# R602H.net
KiCad netlist of a schematic drawn in EAGLE
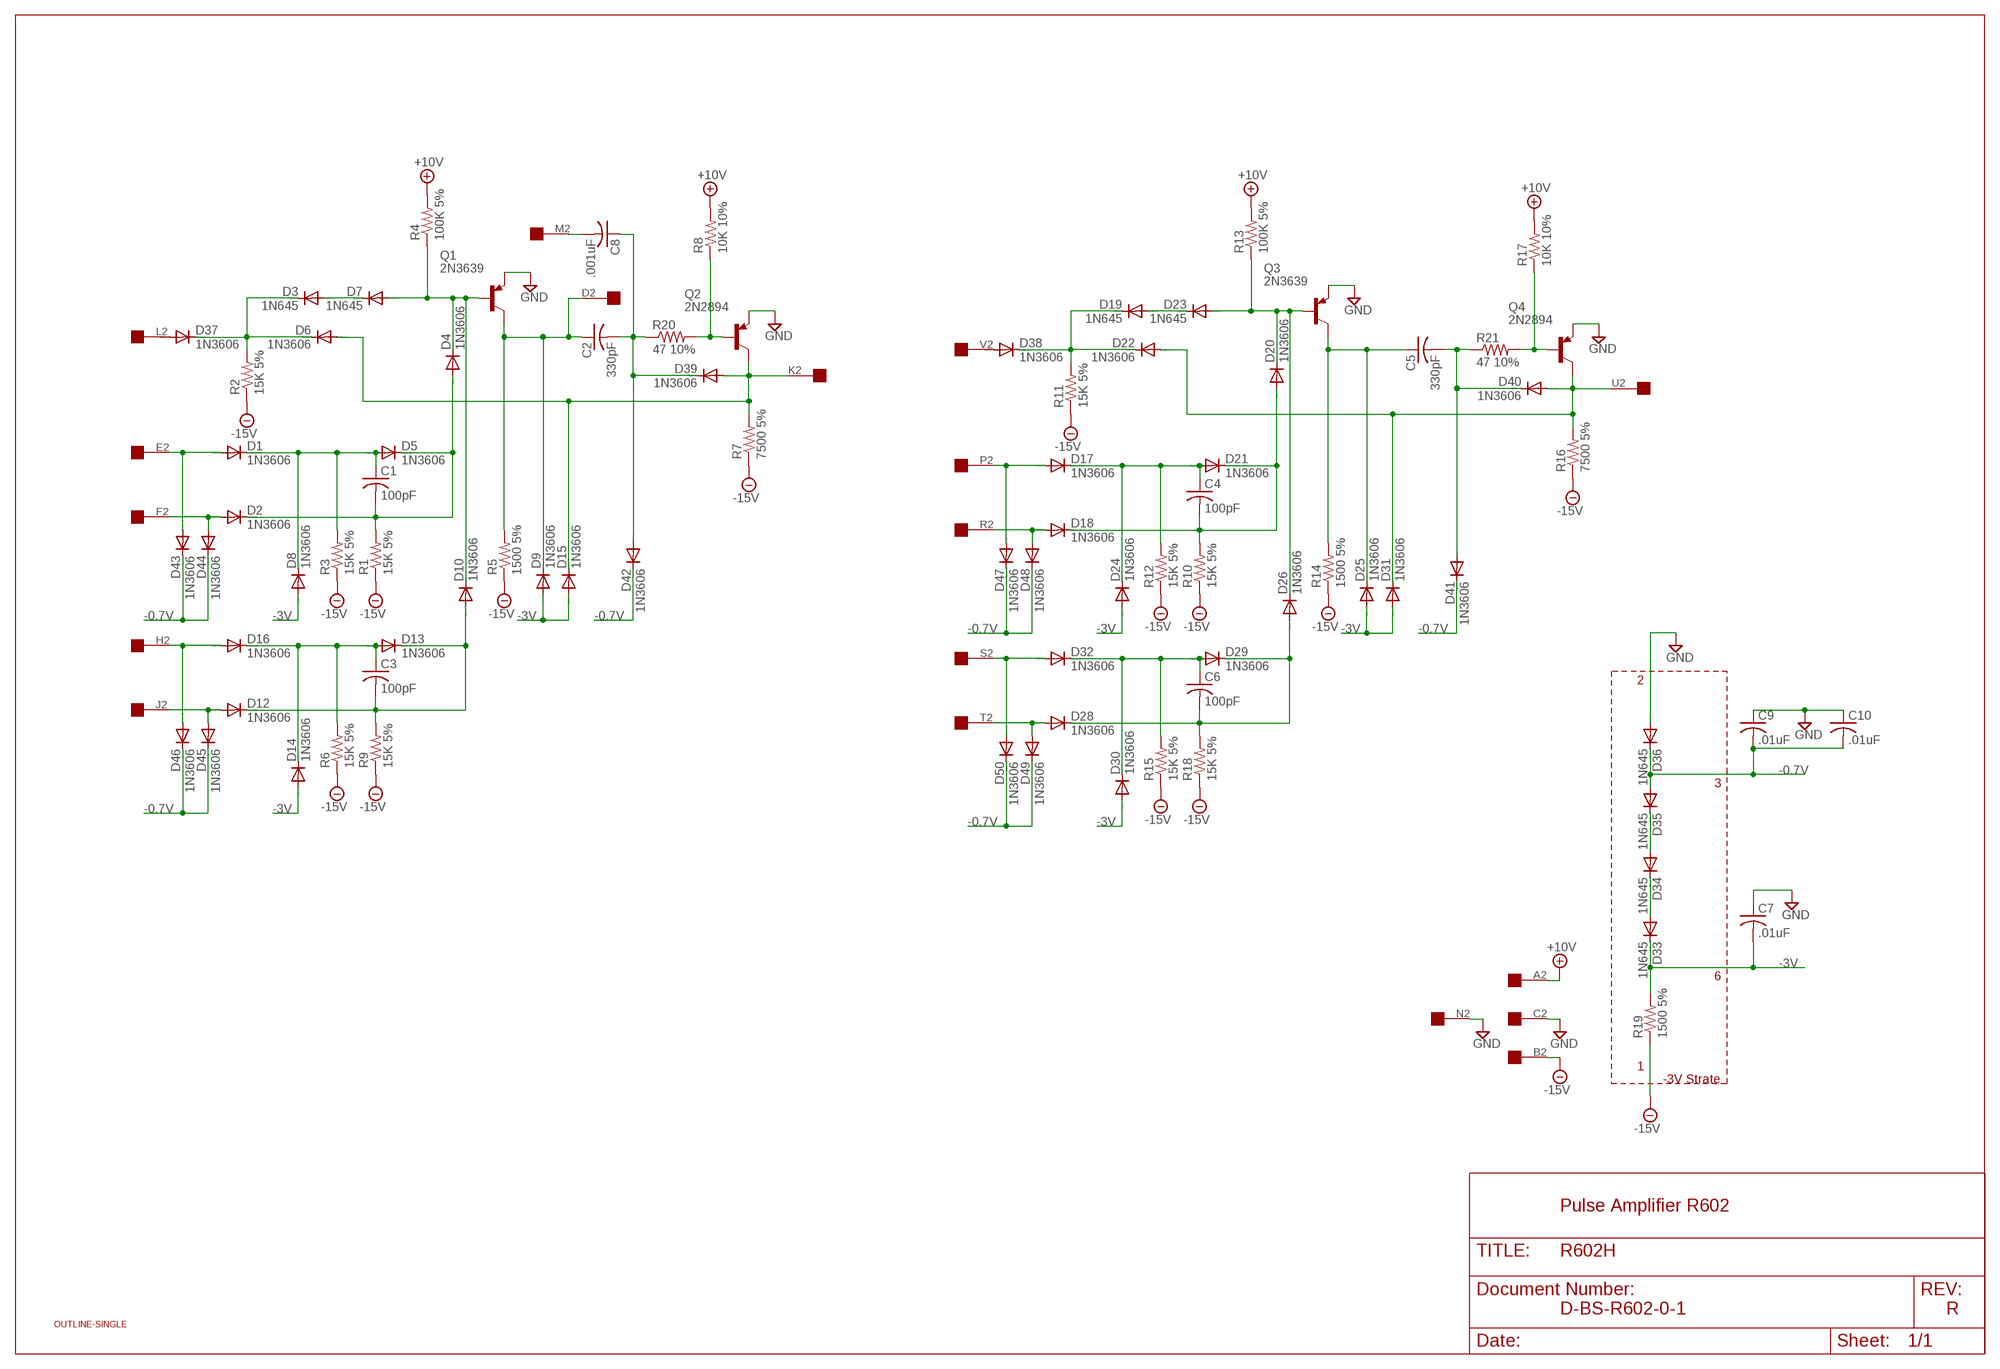
[diagram p0: schematic, sheet 1]

(export (version "E")
  (design (tool "Eeschema 10.0.6"))
  (components
    (comp (ref "C1")
      (value "100pF")
      (footprint "eagle-import:C050-025X075")
      (libsource (lib "eagle-import") (part "C-US050-025X075"))
    )
    (comp (ref "C2")
      (value "330pF")
      (footprint "eagle-import:C050-025X075")
      (libsource (lib "eagle-import") (part "C-US050-025X075"))
    )
    (comp (ref "C3")
      (value "100pF")
      (footprint "eagle-import:C050-025X075")
      (libsource (lib "eagle-import") (part "C-US050-025X075"))
    )
    (comp (ref "C4")
      (value "100pF")
      (footprint "eagle-import:C050-025X075")
      (libsource (lib "eagle-import") (part "C-US050-025X075"))
    )
    (comp (ref "C5")
      (value "330pF")
      (footprint "eagle-import:C050-025X075")
      (libsource (lib "eagle-import") (part "C-US050-025X075"))
    )
    (comp (ref "C6")
      (value "100pF")
      (footprint "eagle-import:C050-025X075")
      (libsource (lib "eagle-import") (part "C-US050-025X075"))
    )
    (comp (ref "C7")
      (value ".01uF")
      (footprint "eagle-import:C075-032X103")
      (libsource (lib "eagle-import") (part "C-US075-032X103"))
    )
    (comp (ref "C8")
      (value ".001uF")
      (footprint "eagle-import:C050-025X075")
      (libsource (lib "eagle-import") (part "C-US050-025X075"))
    )
    (comp (ref "C9")
      (value ".01uF")
      (footprint "eagle-import:C050-025X075")
      (libsource (lib "eagle-import") (part "C-US050-025X075"))
    )
    (comp (ref "C10")
      (value ".01uF")
      (footprint "eagle-import:C050-025X075")
      (libsource (lib "eagle-import") (part "C-US050-025X075"))
    )
    (comp (ref "D1")
      (value "1N3606")
      (footprint "eagle-import:DO35-10")
      (libsource (lib "eagle-import") (part "1N4148DO35-10"))
    )
    (comp (ref "D2")
      (value "1N3606")
      (footprint "eagle-import:DO35-10")
      (libsource (lib "eagle-import") (part "1N4148DO35-10"))
    )
    (comp (ref "D3")
      (value "1N645")
      (footprint "eagle-import:DO35-10")
      (libsource (lib "eagle-import") (part "1N4148DO35-10"))
    )
    (comp (ref "D4")
      (value "1N3606")
      (footprint "eagle-import:DO35-10")
      (libsource (lib "eagle-import") (part "1N4148DO35-10"))
    )
    (comp (ref "D5")
      (value "1N3606")
      (footprint "eagle-import:DO35-10")
      (libsource (lib "eagle-import") (part "1N4148DO35-10"))
    )
    (comp (ref "D6")
      (value "1N3606")
      (footprint "eagle-import:DO35-10")
      (libsource (lib "eagle-import") (part "1N4148DO35-10"))
    )
    (comp (ref "D7")
      (value "1N645")
      (footprint "eagle-import:DO35-10")
      (libsource (lib "eagle-import") (part "1N4148DO35-10"))
    )
    (comp (ref "D8")
      (value "1N3606")
      (footprint "eagle-import:DO35-10")
      (libsource (lib "eagle-import") (part "1N4148DO35-10"))
    )
    (comp (ref "D9")
      (value "1N3606")
      (footprint "eagle-import:DO35-10")
      (libsource (lib "eagle-import") (part "1N4148DO35-10"))
    )
    (comp (ref "D10")
      (value "1N3606")
      (footprint "eagle-import:DO35-10")
      (libsource (lib "eagle-import") (part "1N4148DO35-10"))
    )
    (comp (ref "D12")
      (value "1N3606")
      (footprint "eagle-import:DO35-10")
      (libsource (lib "eagle-import") (part "1N4148DO35-10"))
    )
    (comp (ref "D13")
      (value "1N3606")
      (footprint "eagle-import:DO35-10")
      (libsource (lib "eagle-import") (part "1N4148DO35-10"))
    )
    (comp (ref "D14")
      (value "1N3606")
      (footprint "eagle-import:DO35-10")
      (libsource (lib "eagle-import") (part "1N4148DO35-10"))
    )
    (comp (ref "D15")
      (value "1N3606")
      (footprint "eagle-import:DO35-10")
      (libsource (lib "eagle-import") (part "1N4148DO35-10"))
    )
    (comp (ref "D16")
      (value "1N3606")
      (footprint "eagle-import:DO35-10")
      (libsource (lib "eagle-import") (part "1N4148DO35-10"))
    )
    (comp (ref "D17")
      (value "1N3606")
      (footprint "eagle-import:DO35-10")
      (libsource (lib "eagle-import") (part "1N4148DO35-10"))
    )
    (comp (ref "D18")
      (value "1N3606")
      (footprint "eagle-import:DO35-10")
      (libsource (lib "eagle-import") (part "1N4148DO35-10"))
    )
    (comp (ref "D19")
      (value "1N645")
      (footprint "eagle-import:DO35-10")
      (libsource (lib "eagle-import") (part "1N4148DO35-10"))
    )
    (comp (ref "D20")
      (value "1N3606")
      (footprint "eagle-import:DO35-10")
      (libsource (lib "eagle-import") (part "1N4148DO35-10"))
    )
    (comp (ref "D21")
      (value "1N3606")
      (footprint "eagle-import:DO35-10")
      (libsource (lib "eagle-import") (part "1N4148DO35-10"))
    )
    (comp (ref "D22")
      (value "1N3606")
      (footprint "eagle-import:DO35-10")
      (libsource (lib "eagle-import") (part "1N4148DO35-10"))
    )
    (comp (ref "D23")
      (value "1N645")
      (footprint "eagle-import:DO35-10")
      (libsource (lib "eagle-import") (part "1N4148DO35-10"))
    )
    (comp (ref "D24")
      (value "1N3606")
      (footprint "eagle-import:DO35-10")
      (libsource (lib "eagle-import") (part "1N4148DO35-10"))
    )
    (comp (ref "D25")
      (value "1N3606")
      (footprint "eagle-import:DO35-10")
      (libsource (lib "eagle-import") (part "1N4148DO35-10"))
    )
    (comp (ref "D26")
      (value "1N3606")
      (footprint "eagle-import:DO35-10")
      (libsource (lib "eagle-import") (part "1N4148DO35-10"))
    )
    (comp (ref "D28")
      (value "1N3606")
      (footprint "eagle-import:DO35-10")
      (libsource (lib "eagle-import") (part "1N4148DO35-10"))
    )
    (comp (ref "D29")
      (value "1N3606")
      (footprint "eagle-import:DO35-10")
      (libsource (lib "eagle-import") (part "1N4148DO35-10"))
    )
    (comp (ref "D30")
      (value "1N3606")
      (footprint "eagle-import:DO35-10")
      (libsource (lib "eagle-import") (part "1N4148DO35-10"))
    )
    (comp (ref "D31")
      (value "1N3606")
      (footprint "eagle-import:DO35-10")
      (libsource (lib "eagle-import") (part "1N4148DO35-10"))
    )
    (comp (ref "D32")
      (value "1N3606")
      (footprint "eagle-import:DO35-10")
      (libsource (lib "eagle-import") (part "1N4148DO35-10"))
    )
    (comp (ref "D33")
      (value "1N645")
      (footprint "eagle-import:DO35-10")
      (libsource (lib "eagle-import") (part "1N4148DO35-10"))
    )
    (comp (ref "D34")
      (value "1N645")
      (footprint "eagle-import:DO35-10")
      (libsource (lib "eagle-import") (part "1N4148DO35-10"))
    )
    (comp (ref "D35")
      (value "1N645")
      (footprint "eagle-import:DO35-10")
      (libsource (lib "eagle-import") (part "1N4148DO35-10"))
    )
    (comp (ref "D36")
      (value "1N645")
      (footprint "eagle-import:DO35-10")
      (libsource (lib "eagle-import") (part "1N4148DO35-10"))
    )
    (comp (ref "D37")
      (value "1N3606")
      (footprint "eagle-import:DO35-10")
      (libsource (lib "eagle-import") (part "1N4148DO35-10"))
    )
    (comp (ref "D38")
      (value "1N3606")
      (footprint "eagle-import:DO35-10")
      (libsource (lib "eagle-import") (part "1N4148DO35-10"))
    )
    (comp (ref "D39")
      (value "1N3606")
      (footprint "eagle-import:DO35-10")
      (libsource (lib "eagle-import") (part "1N4148DO35-10"))
    )
    (comp (ref "D40")
      (value "1N3606")
      (footprint "eagle-import:DO35-10")
      (libsource (lib "eagle-import") (part "1N4148DO35-10"))
    )
    (comp (ref "D41")
      (value "1N3606")
      (footprint "eagle-import:DO35-10")
      (libsource (lib "eagle-import") (part "1N4148DO35-10"))
    )
    (comp (ref "D42")
      (value "1N3606")
      (footprint "eagle-import:DO35-10")
      (libsource (lib "eagle-import") (part "1N4148DO35-10"))
    )
    (comp (ref "D43")
      (value "1N3606")
      (footprint "eagle-import:DO35-10")
      (libsource (lib "eagle-import") (part "1N4148DO35-10"))
    )
    (comp (ref "D44")
      (value "1N3606")
      (footprint "eagle-import:DO35-10")
      (libsource (lib "eagle-import") (part "1N4148DO35-10"))
    )
    (comp (ref "D45")
      (value "1N3606")
      (footprint "eagle-import:DO35-10")
      (libsource (lib "eagle-import") (part "1N4148DO35-10"))
    )
    (comp (ref "D46")
      (value "1N3606")
      (footprint "eagle-import:DO35-10")
      (libsource (lib "eagle-import") (part "1N4148DO35-10"))
    )
    (comp (ref "D47")
      (value "1N3606")
      (footprint "eagle-import:DO35-10")
      (libsource (lib "eagle-import") (part "1N4148DO35-10"))
    )
    (comp (ref "D48")
      (value "1N3606")
      (footprint "eagle-import:DO35-10")
      (libsource (lib "eagle-import") (part "1N4148DO35-10"))
    )
    (comp (ref "D49")
      (value "1N3606")
      (footprint "eagle-import:DO35-10")
      (libsource (lib "eagle-import") (part "1N4148DO35-10"))
    )
    (comp (ref "D50")
      (value "1N3606")
      (footprint "eagle-import:DO35-10")
      (libsource (lib "eagle-import") (part "1N4148DO35-10"))
    )
    (comp (ref "Q1")
      (value "2N3639")
      (footprint "eagle-import:TO39")
      (libsource (lib "eagle-import") (part "2N2904"))
    )
    (comp (ref "Q2")
      (value "2N2894")
      (footprint "eagle-import:TO39")
      (libsource (lib "eagle-import") (part "2N2904"))
    )
    (comp (ref "Q3")
      (value "2N3639")
      (footprint "eagle-import:TO39")
      (libsource (lib "eagle-import") (part "2N2904"))
    )
    (comp (ref "Q4")
      (value "2N2894")
      (footprint "eagle-import:TO39")
      (libsource (lib "eagle-import") (part "2N2904"))
    )
    (comp (ref "R1")
      (value "15K 5%")
      (footprint "eagle-import:0207_10")
      (libsource (lib "eagle-import") (part "R-US_0207/10"))
    )
    (comp (ref "R2")
      (value "15K 5%")
      (footprint "eagle-import:0207_10")
      (libsource (lib "eagle-import") (part "R-US_0207/10"))
    )
    (comp (ref "R3")
      (value "15K 5%")
      (footprint "eagle-import:0207_10")
      (libsource (lib "eagle-import") (part "R-US_0207/10"))
    )
    (comp (ref "R4")
      (value "100K 5%")
      (footprint "eagle-import:0207_10")
      (libsource (lib "eagle-import") (part "R-US_0207/10"))
    )
    (comp (ref "R5")
      (value "1500 5%")
      (footprint "eagle-import:0207_10")
      (libsource (lib "eagle-import") (part "R-US_0207/10"))
    )
    (comp (ref "R6")
      (value "15K 5%")
      (footprint "eagle-import:0207_10")
      (libsource (lib "eagle-import") (part "R-US_0207/10"))
    )
    (comp (ref "R7")
      (value "7500 5%")
      (footprint "eagle-import:0207_10")
      (libsource (lib "eagle-import") (part "R-US_0207/10"))
    )
    (comp (ref "R8")
      (value "10K 10%")
      (footprint "eagle-import:0207_10")
      (libsource (lib "eagle-import") (part "R-US_0207/10"))
    )
    (comp (ref "R9")
      (value "15K 5%")
      (footprint "eagle-import:0207_10")
      (libsource (lib "eagle-import") (part "R-US_0207/10"))
    )
    (comp (ref "R10")
      (value "15K 5%")
      (footprint "eagle-import:0207_10")
      (libsource (lib "eagle-import") (part "R-US_0207/10"))
    )
    (comp (ref "R11")
      (value "15K 5%")
      (footprint "eagle-import:0207_10")
      (libsource (lib "eagle-import") (part "R-US_0207/10"))
    )
    (comp (ref "R12")
      (value "15K 5%")
      (footprint "eagle-import:0207_10")
      (libsource (lib "eagle-import") (part "R-US_0207/10"))
    )
    (comp (ref "R13")
      (value "100K 5%")
      (footprint "eagle-import:0207_10")
      (libsource (lib "eagle-import") (part "R-US_0207/10"))
    )
    (comp (ref "R14")
      (value "1500 5%")
      (footprint "eagle-import:0207_10")
      (libsource (lib "eagle-import") (part "R-US_0207/10"))
    )
    (comp (ref "R15")
      (value "15K 5%")
      (footprint "eagle-import:0207_10")
      (libsource (lib "eagle-import") (part "R-US_0207/10"))
    )
    (comp (ref "R16")
      (value "7500 5%")
      (footprint "eagle-import:0207_10")
      (libsource (lib "eagle-import") (part "R-US_0207/10"))
    )
    (comp (ref "R17")
      (value "10K 10%")
      (footprint "eagle-import:0207_10")
      (libsource (lib "eagle-import") (part "R-US_0207/10"))
    )
    (comp (ref "R18")
      (value "15K 5%")
      (footprint "eagle-import:0207_10")
      (libsource (lib "eagle-import") (part "R-US_0207/10"))
    )
    (comp (ref "R19")
      (value "1500 5%")
      (footprint "eagle-import:0207_10")
      (libsource (lib "eagle-import") (part "R-US_0207/10"))
    )
    (comp (ref "R20")
      (value "47 10%")
      (footprint "eagle-import:0207_10")
      (libsource (lib "eagle-import") (part "R-US_0207/10"))
    )
    (comp (ref "R21")
      (value "47 10%")
      (footprint "eagle-import:0207_10")
      (libsource (lib "eagle-import") (part "R-US_0207/10"))
    )
    (comp (ref "U$1")
      (value "OUTLINE-SINGLE")
      (footprint "eagle-import:SINGLE")
      (libsource (lib "eagle-import") (part "OUTLINE-SINGLE"))
    )
    (comp (ref "U$2")
      (value "EDGE-1")
      (footprint "eagle-import:EDGE-CON1")
      (libsource (lib "eagle-import") (part "EDGE-1"))
    )
  )
  (nets
    (net (code "1") (name "+10V") (class "Default")
      (node (ref "R13") (pin "2") (pinfunction "2_2") (pintype "passive"))
      (node (ref "R17") (pin "2") (pinfunction "2_2") (pintype "passive"))
      (node (ref "R4") (pin "2") (pinfunction "2_2") (pintype "passive"))
      (node (ref "R8") (pin "2") (pinfunction "2_2") (pintype "passive"))
      (node (ref "U$2") (pin "A2") (pinfunction "1_A2") (pintype "bidirectional"))
    )
    (net (code "2") (name "-15V") (class "Default")
      (node (ref "R1") (pin "1") (pinfunction "1_1") (pintype "passive"))
      (node (ref "R10") (pin "1") (pinfunction "1_1") (pintype "passive"))
      (node (ref "R11") (pin "1") (pinfunction "1_1") (pintype "passive"))
      (node (ref "R12") (pin "1") (pinfunction "1_1") (pintype "passive"))
      (node (ref "R14") (pin "1") (pinfunction "1_1") (pintype "passive"))
      (node (ref "R15") (pin "1") (pinfunction "1_1") (pintype "passive"))
      (node (ref "R16") (pin "1") (pinfunction "1_1") (pintype "passive"))
      (node (ref "R18") (pin "1") (pinfunction "1_1") (pintype "passive"))
      (node (ref "R19") (pin "1") (pinfunction "1_1") (pintype "passive"))
      (node (ref "R2") (pin "1") (pinfunction "1_1") (pintype "passive"))
      (node (ref "R3") (pin "1") (pinfunction "1_1") (pintype "passive"))
      (node (ref "R5") (pin "1") (pinfunction "1_1") (pintype "passive"))
      (node (ref "R6") (pin "1") (pinfunction "1_1") (pintype "passive"))
      (node (ref "R7") (pin "1") (pinfunction "1_1") (pintype "passive"))
      (node (ref "R9") (pin "1") (pinfunction "1_1") (pintype "passive"))
      (node (ref "U$2") (pin "B2") (pinfunction "1_B2") (pintype "bidirectional"))
    )
    (net (code "3") (name "/-0.7V") (class "Default")
      (node (ref "C10") (pin "2") (pinfunction "2_2") (pintype "passive"))
      (node (ref "C9") (pin "2") (pinfunction "2_2") (pintype "passive"))
      (node (ref "D35") (pin "A") (pinfunction "A_A") (pintype "passive"))
      (node (ref "D36") (pin "C") (pinfunction "C_C") (pintype "passive"))
      (node (ref "D41") (pin "C") (pinfunction "C_C") (pintype "passive"))
      (node (ref "D42") (pin "C") (pinfunction "C_C") (pintype "passive"))
      (node (ref "D43") (pin "C") (pinfunction "C_C") (pintype "passive"))
      (node (ref "D44") (pin "C") (pinfunction "C_C") (pintype "passive"))
      (node (ref "D45") (pin "C") (pinfunction "C_C") (pintype "passive"))
      (node (ref "D46") (pin "C") (pinfunction "C_C") (pintype "passive"))
      (node (ref "D47") (pin "C") (pinfunction "C_C") (pintype "passive"))
      (node (ref "D48") (pin "C") (pinfunction "C_C") (pintype "passive"))
      (node (ref "D49") (pin "C") (pinfunction "C_C") (pintype "passive"))
      (node (ref "D50") (pin "C") (pinfunction "C_C") (pintype "passive"))
    )
    (net (code "4") (name "/-3V") (class "Default")
      (node (ref "C7") (pin "2") (pinfunction "2_2") (pintype "passive"))
      (node (ref "D14") (pin "A") (pinfunction "A_A") (pintype "passive"))
      (node (ref "D15") (pin "A") (pinfunction "A_A") (pintype "passive"))
      (node (ref "D24") (pin "A") (pinfunction "A_A") (pintype "passive"))
      (node (ref "D25") (pin "A") (pinfunction "A_A") (pintype "passive"))
      (node (ref "D30") (pin "A") (pinfunction "A_A") (pintype "passive"))
      (node (ref "D31") (pin "A") (pinfunction "A_A") (pintype "passive"))
      (node (ref "D33") (pin "C") (pinfunction "C_C") (pintype "passive"))
      (node (ref "D8") (pin "A") (pinfunction "A_A") (pintype "passive"))
      (node (ref "D9") (pin "A") (pinfunction "A_A") (pintype "passive"))
      (node (ref "R19") (pin "2") (pinfunction "2_2") (pintype "passive"))
    )
    (net (code "5") (name "GND") (class "Default")
      (node (ref "C10") (pin "1") (pinfunction "1_1") (pintype "passive"))
      (node (ref "C7") (pin "1") (pinfunction "1_1") (pintype "passive"))
      (node (ref "C9") (pin "1") (pinfunction "1_1") (pintype "passive"))
      (node (ref "D36") (pin "A") (pinfunction "A_A") (pintype "passive"))
      (node (ref "Q1") (pin "1") (pinfunction "E_1") (pintype "passive"))
      (node (ref "Q2") (pin "1") (pinfunction "E_1") (pintype "passive"))
      (node (ref "Q3") (pin "1") (pinfunction "E_1") (pintype "passive"))
      (node (ref "Q4") (pin "1") (pinfunction "E_1") (pintype "passive"))
      (node (ref "U$2") (pin "C2") (pinfunction "1_C2") (pintype "bidirectional"))
      (node (ref "U$2") (pin "N2") (pinfunction "1_N2") (pintype "bidirectional"))
    )
    (net (code "6") (name "Net-(C1-Pad1)") (class "Default")
      (node (ref "C1") (pin "1") (pinfunction "1_1") (pintype "passive"))
      (node (ref "D1") (pin "C") (pinfunction "C_C") (pintype "passive"))
      (node (ref "D5") (pin "A") (pinfunction "A_A") (pintype "passive"))
      (node (ref "D8") (pin "C") (pinfunction "C_C") (pintype "passive"))
      (node (ref "R3") (pin "2") (pinfunction "2_2") (pintype "passive"))
    )
    (net (code "7") (name "Net-(C1-Pad2)") (class "Default")
      (node (ref "C1") (pin "2") (pinfunction "2_2") (pintype "passive"))
      (node (ref "D2") (pin "C") (pinfunction "C_C") (pintype "passive"))
      (node (ref "D4") (pin "A") (pinfunction "A_A") (pintype "passive"))
      (node (ref "D5") (pin "C") (pinfunction "C_C") (pintype "passive"))
      (node (ref "R1") (pin "2") (pinfunction "2_2") (pintype "passive"))
    )
    (net (code "8") (name "Net-(C2-Pad2)") (class "Default")
      (node (ref "C2") (pin "2") (pinfunction "2_2") (pintype "passive"))
      (node (ref "C8") (pin "1") (pinfunction "1_1") (pintype "passive"))
      (node (ref "D39") (pin "C") (pinfunction "C_C") (pintype "passive"))
      (node (ref "D42") (pin "A") (pinfunction "A_A") (pintype "passive"))
      (node (ref "R20") (pin "1") (pinfunction "1_1") (pintype "passive"))
    )
    (net (code "9") (name "Net-(C3-Pad1)") (class "Default")
      (node (ref "C3") (pin "1") (pinfunction "1_1") (pintype "passive"))
      (node (ref "D13") (pin "A") (pinfunction "A_A") (pintype "passive"))
      (node (ref "D14") (pin "C") (pinfunction "C_C") (pintype "passive"))
      (node (ref "D16") (pin "C") (pinfunction "C_C") (pintype "passive"))
      (node (ref "R6") (pin "2") (pinfunction "2_2") (pintype "passive"))
    )
    (net (code "10") (name "Net-(C3-Pad2)") (class "Default")
      (node (ref "C3") (pin "2") (pinfunction "2_2") (pintype "passive"))
      (node (ref "D10") (pin "A") (pinfunction "A_A") (pintype "passive"))
      (node (ref "D12") (pin "C") (pinfunction "C_C") (pintype "passive"))
      (node (ref "D13") (pin "C") (pinfunction "C_C") (pintype "passive"))
      (node (ref "R9") (pin "2") (pinfunction "2_2") (pintype "passive"))
    )
    (net (code "11") (name "Net-(C4-Pad1)") (class "Default")
      (node (ref "C4") (pin "1") (pinfunction "1_1") (pintype "passive"))
      (node (ref "D17") (pin "C") (pinfunction "C_C") (pintype "passive"))
      (node (ref "D21") (pin "A") (pinfunction "A_A") (pintype "passive"))
      (node (ref "D24") (pin "C") (pinfunction "C_C") (pintype "passive"))
      (node (ref "R12") (pin "2") (pinfunction "2_2") (pintype "passive"))
    )
    (net (code "12") (name "Net-(C4-Pad2)") (class "Default")
      (node (ref "C4") (pin "2") (pinfunction "2_2") (pintype "passive"))
      (node (ref "D18") (pin "C") (pinfunction "C_C") (pintype "passive"))
      (node (ref "D20") (pin "A") (pinfunction "A_A") (pintype "passive"))
      (node (ref "D21") (pin "C") (pinfunction "C_C") (pintype "passive"))
      (node (ref "R10") (pin "2") (pinfunction "2_2") (pintype "passive"))
    )
    (net (code "13") (name "Net-(C5-Pad2)") (class "Default")
      (node (ref "C5") (pin "2") (pinfunction "2_2") (pintype "passive"))
      (node (ref "D40") (pin "C") (pinfunction "C_C") (pintype "passive"))
      (node (ref "D41") (pin "A") (pinfunction "A_A") (pintype "passive"))
      (node (ref "R21") (pin "1") (pinfunction "1_1") (pintype "passive"))
    )
    (net (code "14") (name "Net-(C6-Pad1)") (class "Default")
      (node (ref "C6") (pin "1") (pinfunction "1_1") (pintype "passive"))
      (node (ref "D29") (pin "A") (pinfunction "A_A") (pintype "passive"))
      (node (ref "D30") (pin "C") (pinfunction "C_C") (pintype "passive"))
      (node (ref "D32") (pin "C") (pinfunction "C_C") (pintype "passive"))
      (node (ref "R15") (pin "2") (pinfunction "2_2") (pintype "passive"))
    )
    (net (code "15") (name "Net-(C6-Pad2)") (class "Default")
      (node (ref "C6") (pin "2") (pinfunction "2_2") (pintype "passive"))
      (node (ref "D26") (pin "A") (pinfunction "A_A") (pintype "passive"))
      (node (ref "D28") (pin "C") (pinfunction "C_C") (pintype "passive"))
      (node (ref "D29") (pin "C") (pinfunction "C_C") (pintype "passive"))
      (node (ref "R18") (pin "2") (pinfunction "2_2") (pintype "passive"))
    )
    (net (code "16") (name "Net-(D3-PadA)") (class "Default")
      (node (ref "D3") (pin "A") (pinfunction "A_A") (pintype "passive"))
      (node (ref "D7") (pin "C") (pinfunction "C_C") (pintype "passive"))
    )
    (net (code "17") (name "Net-(D3-PadC)") (class "Default")
      (node (ref "D3") (pin "C") (pinfunction "C_C") (pintype "passive"))
      (node (ref "D37") (pin "C") (pinfunction "C_C") (pintype "passive"))
      (node (ref "D6") (pin "C") (pinfunction "C_C") (pintype "passive"))
      (node (ref "R2") (pin "2") (pinfunction "2_2") (pintype "passive"))
    )
    (net (code "18") (name "Net-(D19-PadA)") (class "Default")
      (node (ref "D19") (pin "A") (pinfunction "A_A") (pintype "passive"))
      (node (ref "D23") (pin "C") (pinfunction "C_C") (pintype "passive"))
    )
    (net (code "19") (name "Net-(D19-PadC)") (class "Default")
      (node (ref "D19") (pin "C") (pinfunction "C_C") (pintype "passive"))
      (node (ref "D22") (pin "C") (pinfunction "C_C") (pintype "passive"))
      (node (ref "D38") (pin "C") (pinfunction "C_C") (pintype "passive"))
      (node (ref "R11") (pin "2") (pinfunction "2_2") (pintype "passive"))
    )
    (net (code "20") (name "Net-(D33-PadA)") (class "Default")
      (node (ref "D33") (pin "A") (pinfunction "A_A") (pintype "passive"))
      (node (ref "D34") (pin "C") (pinfunction "C_C") (pintype "passive"))
    )
    (net (code "21") (name "Net-(D34-PadA)") (class "Default")
      (node (ref "D34") (pin "A") (pinfunction "A_A") (pintype "passive"))
      (node (ref "D35") (pin "C") (pinfunction "C_C") (pintype "passive"))
    )
    (net (code "22") (name "Net-(Q1-B)") (class "Default")
      (node (ref "D10") (pin "C") (pinfunction "C_C") (pintype "passive"))
      (node (ref "D4") (pin "C") (pinfunction "C_C") (pintype "passive"))
      (node (ref "D7") (pin "A") (pinfunction "A_A") (pintype "passive"))
      (node (ref "Q1") (pin "2") (pinfunction "B_2") (pintype "passive"))
      (node (ref "R4") (pin "1") (pinfunction "1_1") (pintype "passive"))
    )
    (net (code "23") (name "Net-(Q1-C)") (class "Default")
      (node (ref "C2") (pin "1") (pinfunction "1_1") (pintype "passive"))
      (node (ref "D9") (pin "C") (pinfunction "C_C") (pintype "passive"))
      (node (ref "Q1") (pin "3") (pinfunction "C_3") (pintype "passive"))
      (node (ref "R5") (pin "2") (pinfunction "2_2") (pintype "passive"))
      (node (ref "U$2") (pin "D2") (pinfunction "1_D2") (pintype "bidirectional"))
    )
    (net (code "24") (name "Net-(Q2-B)") (class "Default")
      (node (ref "Q2") (pin "2") (pinfunction "B_2") (pintype "passive"))
      (node (ref "R20") (pin "2") (pinfunction "2_2") (pintype "passive"))
      (node (ref "R8") (pin "1") (pinfunction "1_1") (pintype "passive"))
    )
    (net (code "25") (name "Net-(Q2-C)") (class "Default")
      (node (ref "D15") (pin "C") (pinfunction "C_C") (pintype "passive"))
      (node (ref "D39") (pin "A") (pinfunction "A_A") (pintype "passive"))
      (node (ref "D6") (pin "A") (pinfunction "A_A") (pintype "passive"))
      (node (ref "Q2") (pin "3") (pinfunction "C_3") (pintype "passive"))
      (node (ref "R7") (pin "2") (pinfunction "2_2") (pintype "passive"))
      (node (ref "U$2") (pin "K2") (pinfunction "1_K2") (pintype "bidirectional"))
    )
    (net (code "26") (name "Net-(Q3-B)") (class "Default")
      (node (ref "D20") (pin "C") (pinfunction "C_C") (pintype "passive"))
      (node (ref "D23") (pin "A") (pinfunction "A_A") (pintype "passive"))
      (node (ref "D26") (pin "C") (pinfunction "C_C") (pintype "passive"))
      (node (ref "Q3") (pin "2") (pinfunction "B_2") (pintype "passive"))
      (node (ref "R13") (pin "1") (pinfunction "1_1") (pintype "passive"))
    )
    (net (code "27") (name "Net-(Q3-C)") (class "Default")
      (node (ref "C5") (pin "1") (pinfunction "1_1") (pintype "passive"))
      (node (ref "D25") (pin "C") (pinfunction "C_C") (pintype "passive"))
      (node (ref "Q3") (pin "3") (pinfunction "C_3") (pintype "passive"))
      (node (ref "R14") (pin "2") (pinfunction "2_2") (pintype "passive"))
    )
    (net (code "28") (name "Net-(Q4-B)") (class "Default")
      (node (ref "Q4") (pin "2") (pinfunction "B_2") (pintype "passive"))
      (node (ref "R17") (pin "1") (pinfunction "1_1") (pintype "passive"))
      (node (ref "R21") (pin "2") (pinfunction "2_2") (pintype "passive"))
    )
    (net (code "29") (name "Net-(Q4-C)") (class "Default")
      (node (ref "D22") (pin "A") (pinfunction "A_A") (pintype "passive"))
      (node (ref "D31") (pin "C") (pinfunction "C_C") (pintype "passive"))
      (node (ref "D40") (pin "A") (pinfunction "A_A") (pintype "passive"))
      (node (ref "Q4") (pin "3") (pinfunction "C_3") (pintype "passive"))
      (node (ref "R16") (pin "2") (pinfunction "2_2") (pintype "passive"))
      (node (ref "U$2") (pin "U2") (pinfunction "1_U2") (pintype "bidirectional"))
    )
    (net (code "30") (name "Net-(U$2E-1)") (class "Default")
      (node (ref "D1") (pin "A") (pinfunction "A_A") (pintype "passive"))
      (node (ref "D43") (pin "A") (pinfunction "A_A") (pintype "passive"))
      (node (ref "U$2") (pin "E2") (pinfunction "1_E2") (pintype "bidirectional"))
    )
    (net (code "31") (name "Net-(U$2F-1)") (class "Default")
      (node (ref "D2") (pin "A") (pinfunction "A_A") (pintype "passive"))
      (node (ref "D44") (pin "A") (pinfunction "A_A") (pintype "passive"))
      (node (ref "U$2") (pin "F2") (pinfunction "1_F2") (pintype "bidirectional"))
    )
    (net (code "32") (name "Net-(U$2G-1)") (class "Default")
      (node (ref "D16") (pin "A") (pinfunction "A_A") (pintype "passive"))
      (node (ref "D46") (pin "A") (pinfunction "A_A") (pintype "passive"))
      (node (ref "U$2") (pin "H2") (pinfunction "1_H2") (pintype "bidirectional"))
    )
    (net (code "33") (name "Net-(U$2H-1)") (class "Default")
      (node (ref "D12") (pin "A") (pinfunction "A_A") (pintype "passive"))
      (node (ref "D45") (pin "A") (pinfunction "A_A") (pintype "passive"))
      (node (ref "U$2") (pin "J2") (pinfunction "1_J2") (pintype "bidirectional"))
    )
    (net (code "34") (name "Net-(U$2J-1)") (class "Default")
      (node (ref "D37") (pin "A") (pinfunction "A_A") (pintype "passive"))
      (node (ref "U$2") (pin "L2") (pinfunction "1_L2") (pintype "bidirectional"))
    )
    (net (code "35") (name "Net-(U$2K-1)") (class "Default")
      (node (ref "C8") (pin "2") (pinfunction "2_2") (pintype "passive"))
      (node (ref "U$2") (pin "M2") (pinfunction "1_M2") (pintype "bidirectional"))
    )
    (net (code "36") (name "Net-(U$2M-1)") (class "Default")
      (node (ref "D17") (pin "A") (pinfunction "A_A") (pintype "passive"))
      (node (ref "D47") (pin "A") (pinfunction "A_A") (pintype "passive"))
      (node (ref "U$2") (pin "P2") (pinfunction "1_P2") (pintype "bidirectional"))
    )
    (net (code "37") (name "Net-(U$2N-1)") (class "Default")
      (node (ref "D18") (pin "A") (pinfunction "A_A") (pintype "passive"))
      (node (ref "D48") (pin "A") (pinfunction "A_A") (pintype "passive"))
      (node (ref "U$2") (pin "R2") (pinfunction "1_R2") (pintype "bidirectional"))
    )
    (net (code "38") (name "Net-(U$2O-1)") (class "Default")
      (node (ref "D32") (pin "A") (pinfunction "A_A") (pintype "passive"))
      (node (ref "D50") (pin "A") (pinfunction "A_A") (pintype "passive"))
      (node (ref "U$2") (pin "S2") (pinfunction "1_S2") (pintype "bidirectional"))
    )
    (net (code "39") (name "Net-(U$2P-1)") (class "Default")
      (node (ref "D28") (pin "A") (pinfunction "A_A") (pintype "passive"))
      (node (ref "D49") (pin "A") (pinfunction "A_A") (pintype "passive"))
      (node (ref "U$2") (pin "T2") (pinfunction "1_T2") (pintype "bidirectional"))
    )
    (net (code "40") (name "Net-(U$2R-1)") (class "Default")
      (node (ref "D38") (pin "A") (pinfunction "A_A") (pintype "passive"))
      (node (ref "U$2") (pin "V2") (pinfunction "1_V2") (pintype "bidirectional"))
    )
  )
)
